# main.net
KiCad netlist of a schematic drawn in EAGLE
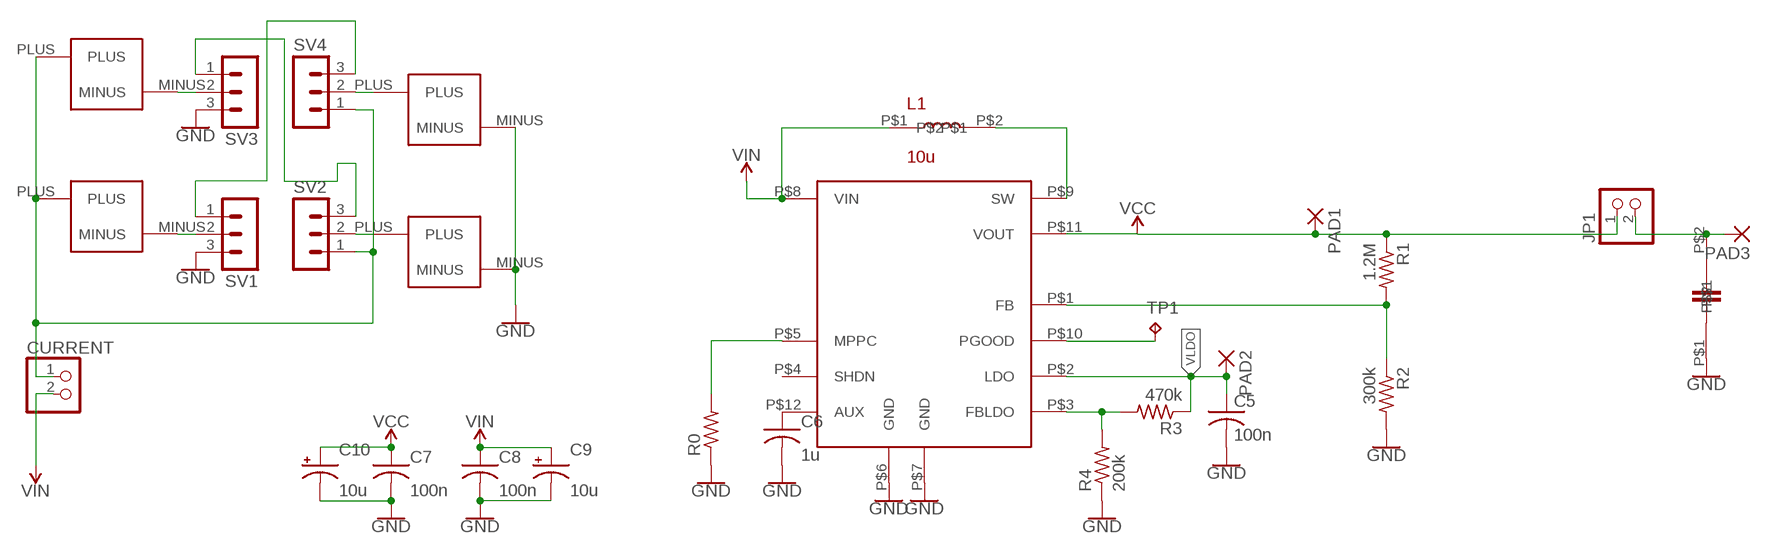
[diagram p0: schematic, sheet 1]

(export (version "E")
  (design (tool "Eeschema 10.0.6"))
  (components
    (comp (ref "C1")
      (value "SOLAR_CELL")
      (footprint "eagle-import:SOLAR_CELL")
      (libsource (lib "eagle-import") (part "SOLAR_CELL"))
    )
    (comp (ref "C2")
      (value "SOLAR_CELL")
      (footprint "eagle-import:SOLAR_CELL")
      (libsource (lib "eagle-import") (part "SOLAR_CELL"))
    )
    (comp (ref "C3")
      (value "SOLAR_CELL")
      (footprint "eagle-import:SOLAR_CELL")
      (libsource (lib "eagle-import") (part "SOLAR_CELL"))
    )
    (comp (ref "C4")
      (value "SOLAR_CELL")
      (footprint "eagle-import:SOLAR_CELL")
      (libsource (lib "eagle-import") (part "SOLAR_CELL"))
    )
    (comp (ref "C5")
      (value "100n")
      (footprint "eagle-import:C0805K")
      (libsource (lib "eagle-import") (part "C-USC0805K"))
    )
    (comp (ref "C6")
      (value "1u")
      (footprint "eagle-import:C0805K")
      (libsource (lib "eagle-import") (part "C-USC0805K"))
    )
    (comp (ref "C7")
      (value "100n")
      (footprint "eagle-import:C0805K")
      (libsource (lib "eagle-import") (part "C-USC0805K"))
    )
    (comp (ref "C8")
      (value "100n")
      (footprint "eagle-import:C0805K")
      (libsource (lib "eagle-import") (part "C-USC0805K"))
    )
    (comp (ref "C9")
      (value "10u")
      (footprint "eagle-import:CT3528")
      (libsource (lib "eagle-import") (part "CPOL-USCT3528"))
    )
    (comp (ref "C10")
      (value "10u")
      (footprint "eagle-import:CT3528")
      (libsource (lib "eagle-import") (part "CPOL-USCT3528"))
    )
    (comp (ref "CURRENT")
      (value "PINHD-1X2")
      (footprint "eagle-import:1X02")
      (libsource (lib "eagle-import") (part "PINHD-1X2"))
    )
    (comp (ref "JP1")
      (value "PINHD-1X2")
      (footprint "eagle-import:1X02")
      (libsource (lib "eagle-import") (part "PINHD-1X2"))
    )
    (comp (ref "L1")
      (value "10u")
      (footprint "eagle-import:DO1813H")
      (libsource (lib "eagle-import") (part "DO1813H"))
    )
    (comp (ref "PAD1")
      (value "2,54/1,0")
      (footprint "eagle-import:2,54_1,0")
      (libsource (lib "eagle-import") (part "2,54/1,0"))
    )
    (comp (ref "PAD2")
      (value "2,54/1,0")
      (footprint "eagle-import:2,54_1,0")
      (libsource (lib "eagle-import") (part "2,54/1,0"))
    )
    (comp (ref "PAD3")
      (value "2,54/1,0")
      (footprint "eagle-import:2,54_1,0")
      (libsource (lib "eagle-import") (part "2,54/1,0"))
    )
    (comp (ref "R0")
      (value "R-US_R0603")
      (footprint "eagle-import:R0603")
      (libsource (lib "eagle-import") (part "R-US_R0603"))
    )
    (comp (ref "R1")
      (value "1.2M")
      (footprint "eagle-import:R0603")
      (libsource (lib "eagle-import") (part "R-US_R0603"))
    )
    (comp (ref "R2")
      (value "300k")
      (footprint "eagle-import:R0603")
      (libsource (lib "eagle-import") (part "R-US_R0603"))
    )
    (comp (ref "R3")
      (value "470k")
      (footprint "eagle-import:R0603")
      (libsource (lib "eagle-import") (part "R-US_R0603"))
    )
    (comp (ref "R4")
      (value "200k")
      (footprint "eagle-import:R0603")
      (libsource (lib "eagle-import") (part "R-US_R0603"))
    )
    (comp (ref "SV1")
      (value "MA03-1")
      (footprint "eagle-import:MA03-1")
      (libsource (lib "eagle-import") (part "MA03-1"))
    )
    (comp (ref "SV2")
      (value "MA03-1")
      (footprint "eagle-import:MA03-1")
      (libsource (lib "eagle-import") (part "MA03-1"))
    )
    (comp (ref "SV3")
      (value "MA03-1")
      (footprint "eagle-import:MA03-1")
      (libsource (lib "eagle-import") (part "MA03-1"))
    )
    (comp (ref "SV4")
      (value "MA03-1")
      (footprint "eagle-import:MA03-1")
      (libsource (lib "eagle-import") (part "MA03-1"))
    )
    (comp (ref "TP1")
      (value "TPTP11SQ")
      (footprint "eagle-import:TP11SQ")
      (libsource (lib "eagle-import") (part "TPTP11SQ"))
    )
    (comp (ref "U$1")
      (value "LTC3105")
      (footprint "eagle-import:MSOP_12")
      (libsource (lib "eagle-import") (part "LTC3105"))
    )
    (comp (ref "U$2")
      (value "SUPERCAP")
      (footprint "eagle-import:SUPERCAP")
      (libsource (lib "eagle-import") (part "SUPERCAP"))
    )
  )
  (nets
    (net (code "1") (name "GND") (class "Default")
      (node (ref "C10") (pin "-") (pinfunction "-_-") (pintype "passive"))
      (node (ref "C2") (pin "MINUS") (pinfunction "MINUS_MINUS") (pintype "bidirectional"))
      (node (ref "C4") (pin "MINUS") (pinfunction "MINUS_MINUS") (pintype "bidirectional"))
      (node (ref "C5") (pin "2") (pinfunction "2_2") (pintype "passive"))
      (node (ref "C6") (pin "2") (pinfunction "2_2") (pintype "passive"))
      (node (ref "C7") (pin "2") (pinfunction "2_2") (pintype "passive"))
      (node (ref "C8") (pin "2") (pinfunction "2_2") (pintype "passive"))
      (node (ref "C9") (pin "-") (pinfunction "-_-") (pintype "passive"))
      (node (ref "R0") (pin "1") (pinfunction "1_1") (pintype "passive"))
      (node (ref "R2") (pin "2") (pinfunction "2_2") (pintype "passive"))
      (node (ref "R4") (pin "1") (pinfunction "1_1") (pintype "passive"))
      (node (ref "SV1") (pin "3") (pinfunction "3_3") (pintype "passive"))
      (node (ref "SV3") (pin "3") (pinfunction "3_3") (pintype "passive"))
      (node (ref "U$1") (pin "P$6") (pinfunction "GND_P$6") (pintype "bidirectional"))
      (node (ref "U$1") (pin "P$7") (pinfunction "GND_P$7") (pintype "bidirectional"))
      (node (ref "U$2") (pin "P$1") (pinfunction "P$1_P$1") (pintype "bidirectional"))
    )
    (net (code "2") (name "Net-(C1-PadMINUS)") (class "Default")
      (node (ref "C1") (pin "MINUS") (pinfunction "MINUS_MINUS") (pintype "bidirectional"))
      (node (ref "SV1") (pin "2") (pinfunction "2_2") (pintype "passive"))
    )
    (net (code "3") (name "Net-(C1-PadPLUS)") (class "Default")
      (node (ref "C1") (pin "PLUS") (pinfunction "PLUS_PLUS") (pintype "bidirectional"))
      (node (ref "C3") (pin "PLUS") (pinfunction "PLUS_PLUS") (pintype "bidirectional"))
      (node (ref "CURRENT") (pin "1") (pinfunction "1_1") (pintype "passive"))
      (node (ref "SV2") (pin "1") (pinfunction "1_1") (pintype "passive"))
      (node (ref "SV4") (pin "1") (pinfunction "1_1") (pintype "passive"))
    )
    (net (code "4") (name "Net-(C2-PadPLUS)") (class "Default")
      (node (ref "C2") (pin "PLUS") (pinfunction "PLUS_PLUS") (pintype "bidirectional"))
      (node (ref "SV2") (pin "2") (pinfunction "2_2") (pintype "passive"))
    )
    (net (code "5") (name "Net-(C3-PadMINUS)") (class "Default")
      (node (ref "C3") (pin "MINUS") (pinfunction "MINUS_MINUS") (pintype "bidirectional"))
      (node (ref "SV3") (pin "2") (pinfunction "2_2") (pintype "passive"))
    )
    (net (code "6") (name "Net-(C4-PadPLUS)") (class "Default")
      (node (ref "C4") (pin "PLUS") (pinfunction "PLUS_PLUS") (pintype "bidirectional"))
      (node (ref "SV4") (pin "2") (pinfunction "2_2") (pintype "passive"))
    )
    (net (code "7") (name "Net-(PAD3-P)") (class "Default")
      (node (ref "JP1") (pin "2") (pinfunction "2_2") (pintype "passive"))
      (node (ref "PAD3") (pin "1") (pinfunction "P_1") (pintype "passive"))
      (node (ref "U$2") (pin "P$2") (pinfunction "P$2_P$2") (pintype "bidirectional"))
    )
    (net (code "8") (name "Net-(SV1-Pad1)") (class "Default")
      (node (ref "SV1") (pin "1") (pinfunction "1_1") (pintype "passive"))
      (node (ref "SV4") (pin "3") (pinfunction "3_3") (pintype "passive"))
    )
    (net (code "9") (name "Net-(SV2-Pad3)") (class "Default")
      (node (ref "SV2") (pin "3") (pinfunction "3_3") (pintype "passive"))
      (node (ref "SV3") (pin "1") (pinfunction "1_1") (pintype "passive"))
    )
    (net (code "10") (name "Net-(U$1-AUX)") (class "Default")
      (node (ref "C6") (pin "1") (pinfunction "1_1") (pintype "passive"))
      (node (ref "U$1") (pin "P$12") (pinfunction "AUX_P$12") (pintype "bidirectional"))
    )
    (net (code "11") (name "Net-(U$1-FB)") (class "Default")
      (node (ref "R1") (pin "2") (pinfunction "2_2") (pintype "passive"))
      (node (ref "R2") (pin "1") (pinfunction "1_1") (pintype "passive"))
      (node (ref "U$1") (pin "P$1") (pinfunction "FB_P$1") (pintype "bidirectional"))
    )
    (net (code "12") (name "Net-(U$1-FBLDO)") (class "Default")
      (node (ref "R3") (pin "2") (pinfunction "2_2") (pintype "passive"))
      (node (ref "R4") (pin "2") (pinfunction "2_2") (pintype "passive"))
      (node (ref "U$1") (pin "P$3") (pinfunction "FBLDO_P$3") (pintype "bidirectional"))
    )
    (net (code "13") (name "Net-(U$1-MPPC)") (class "Default")
      (node (ref "R0") (pin "2") (pinfunction "2_2") (pintype "passive"))
      (node (ref "U$1") (pin "P$5") (pinfunction "MPPC_P$5") (pintype "bidirectional"))
    )
    (net (code "14") (name "Net-(U$1-PGOOD)") (class "Default")
      (node (ref "TP1") (pin "TP") (pinfunction "TP_TP") (pintype "input"))
      (node (ref "U$1") (pin "P$10") (pinfunction "PGOOD_P$10") (pintype "bidirectional"))
    )
    (net (code "15") (name "Net-(U$1-SW)") (class "Default")
      (node (ref "L1") (pin "P$2") (pinfunction "P$2_P$2") (pintype "bidirectional"))
      (node (ref "U$1") (pin "P$9") (pinfunction "SW_P$9") (pintype "bidirectional"))
    )
    (net (code "16") (name "VCC") (class "Default")
      (node (ref "C10") (pin "+") (pinfunction "+_+") (pintype "passive"))
      (node (ref "C7") (pin "1") (pinfunction "1_1") (pintype "passive"))
      (node (ref "JP1") (pin "1") (pinfunction "1_1") (pintype "passive"))
      (node (ref "PAD1") (pin "1") (pinfunction "P_1") (pintype "passive"))
      (node (ref "R1") (pin "1") (pinfunction "1_1") (pintype "passive"))
      (node (ref "U$1") (pin "P$11") (pinfunction "VOUT_P$11") (pintype "bidirectional"))
    )
    (net (code "17") (name "VIN") (class "Default")
      (node (ref "C8") (pin "1") (pinfunction "1_1") (pintype "passive"))
      (node (ref "C9") (pin "+") (pinfunction "+_+") (pintype "passive"))
      (node (ref "CURRENT") (pin "2") (pinfunction "2_2") (pintype "passive"))
      (node (ref "L1") (pin "P$1") (pinfunction "P$1_P$1") (pintype "bidirectional"))
      (node (ref "U$1") (pin "P$8") (pinfunction "VIN_P$8") (pintype "bidirectional"))
    )
    (net (code "18") (name "VLDO") (class "Default")
      (node (ref "C5") (pin "1") (pinfunction "1_1") (pintype "passive"))
      (node (ref "PAD2") (pin "1") (pinfunction "P_1") (pintype "passive"))
      (node (ref "R3") (pin "1") (pinfunction "1_1") (pintype "passive"))
      (node (ref "U$1") (pin "P$2") (pinfunction "LDO_P$2") (pintype "bidirectional"))
    )
    (net (code "19") (name "unconnected-(U$1-SHDN-PadP$4)") (class "Default")
      (node (ref "U$1") (pin "P$4") (pinfunction "SHDN_P$4") (pintype "bidirectional"))
    )
  )
)
